# ME433_BB_SCHEM.net
KiCad netlist of a schematic drawn in EAGLE
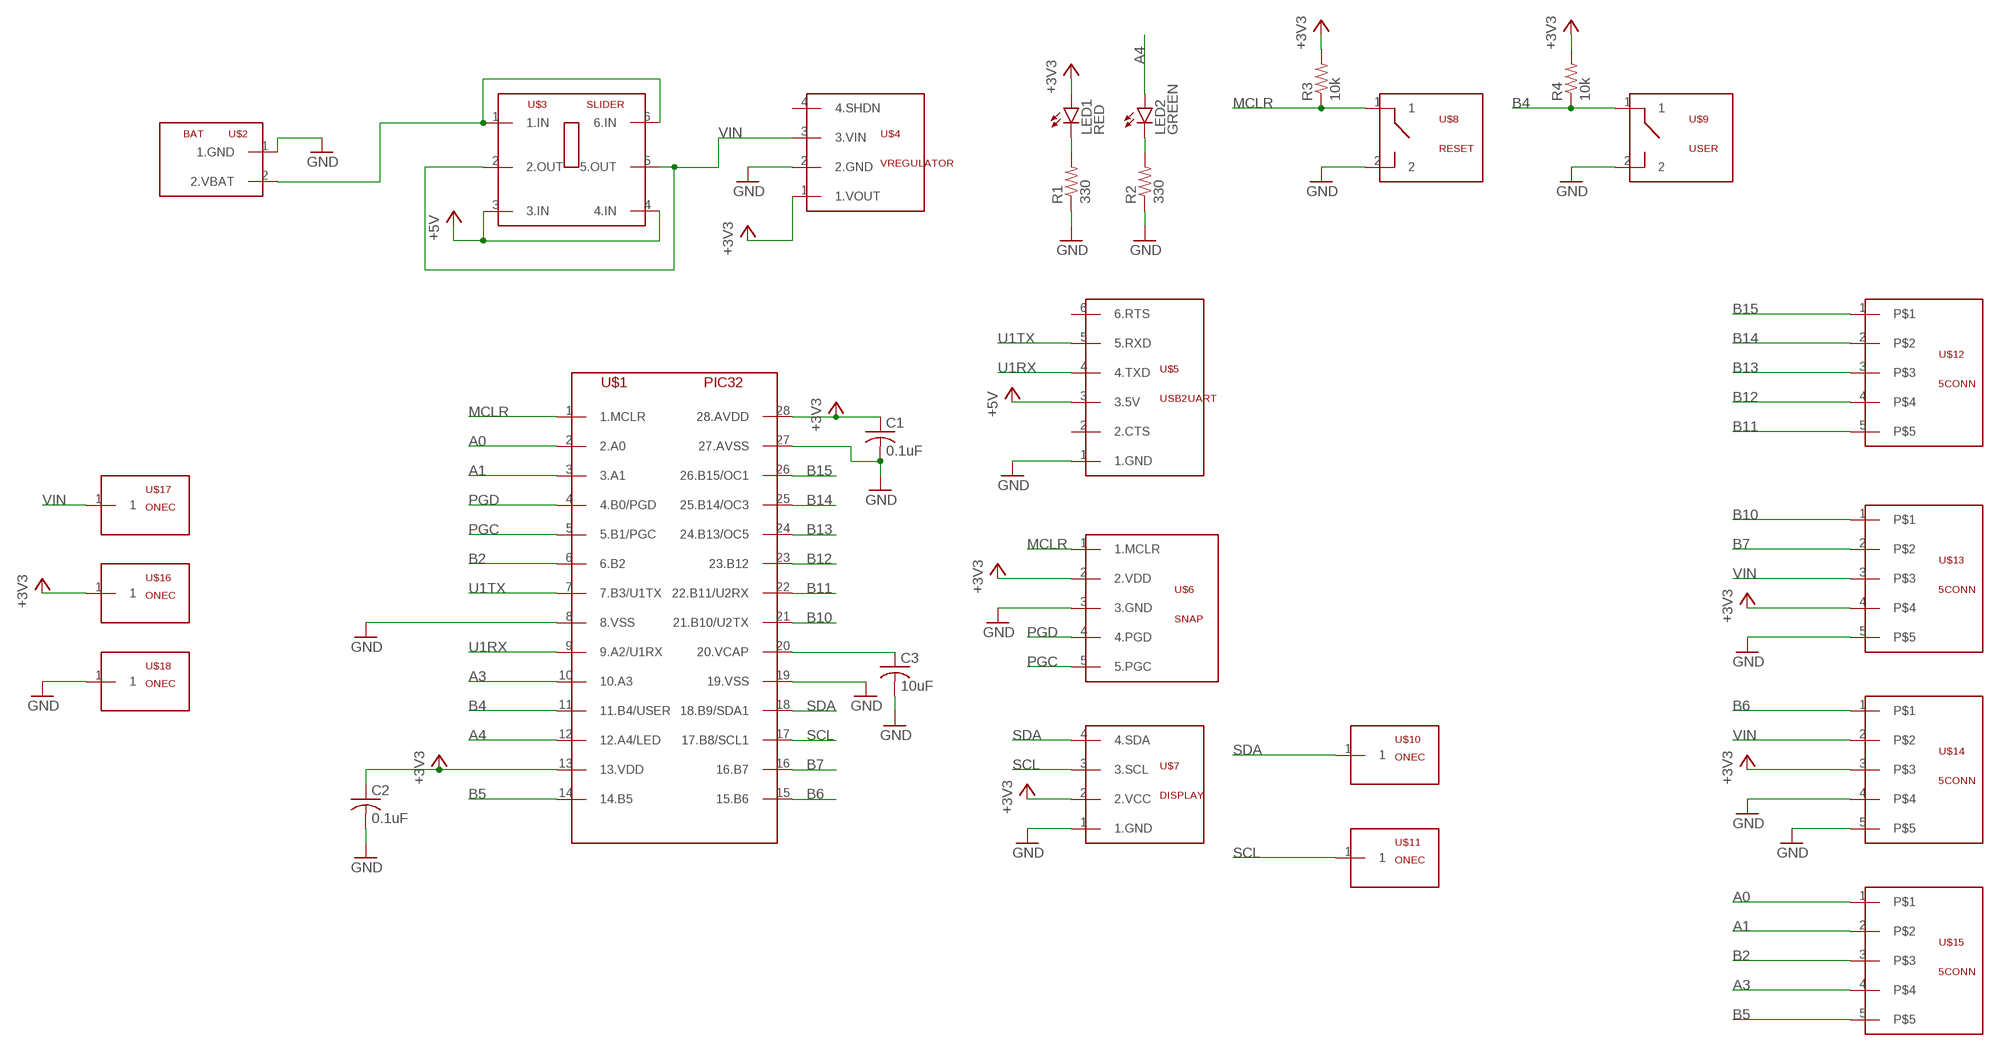
[diagram p0: schematic, sheet 1]

(export (version "E")
  (design (tool "Eeschema 10.0.6"))
  (components
    (comp (ref "C1")
      (value "0.1uF")
      (footprint "eagle-import:C025-024X044")
      (libsource (lib "eagle-import") (part "C-US025-024X044"))
    )
    (comp (ref "C2")
      (value "0.1uF")
      (footprint "eagle-import:C025-024X044")
      (libsource (lib "eagle-import") (part "C-US025-024X044"))
    )
    (comp (ref "C3")
      (value "10uF")
      (footprint "eagle-import:C025-024X044")
      (libsource (lib "eagle-import") (part "C-US025-024X044"))
    )
    (comp (ref "LED1")
      (value "RED")
      (footprint "eagle-import:LED3MM")
      (libsource (lib "eagle-import") (part "LED3MM"))
    )
    (comp (ref "LED2")
      (value "GREEN")
      (footprint "eagle-import:LED3MM")
      (libsource (lib "eagle-import") (part "LED3MM"))
    )
    (comp (ref "R1")
      (value "330")
      (footprint "eagle-import:0207_7")
      (libsource (lib "eagle-import") (part "R-US_0207/7"))
    )
    (comp (ref "R2")
      (value "330")
      (footprint "eagle-import:0207_7")
      (libsource (lib "eagle-import") (part "R-US_0207/7"))
    )
    (comp (ref "R3")
      (value "10k")
      (footprint "eagle-import:0207_7")
      (libsource (lib "eagle-import") (part "R-US_0207/7"))
    )
    (comp (ref "R4")
      (value "10k")
      (footprint "eagle-import:0207_7")
      (libsource (lib "eagle-import") (part "R-US_0207/7"))
    )
    (comp (ref "U$1")
      (value "PIC32")
      (footprint "eagle-import:DIL28-3")
      (libsource (lib "eagle-import") (part "PIC32"))
    )
    (comp (ref "U$2")
      (value "BAT")
      (footprint "eagle-import:BAT")
      (libsource (lib "eagle-import") (part "BAT"))
    )
    (comp (ref "U$3")
      (value "SLIDER")
      (footprint "eagle-import:SLIDER")
      (libsource (lib "eagle-import") (part "SLIDER"))
    )
    (comp (ref "U$4")
      (value "VREGULATOR")
      (footprint "eagle-import:VREGULATOR")
      (libsource (lib "eagle-import") (part "VREGULATOR"))
    )
    (comp (ref "U$5")
      (value "USB2UART")
      (footprint "eagle-import:USB2UART")
      (libsource (lib "eagle-import") (part "USB2UART"))
    )
    (comp (ref "U$6")
      (value "SNAP")
      (footprint "eagle-import:SNAP")
      (libsource (lib "eagle-import") (part "SNAP"))
    )
    (comp (ref "U$7")
      (value "DISPLAY")
      (footprint "eagle-import:DISPLAY")
      (libsource (lib "eagle-import") (part "DISPLAY"))
    )
    (comp (ref "U$8")
      (value "RESET")
      (footprint "eagle-import:BUTT")
      (libsource (lib "eagle-import") (part "BUTT"))
    )
    (comp (ref "U$9")
      (value "USER")
      (footprint "eagle-import:BUTT")
      (libsource (lib "eagle-import") (part "BUTT"))
    )
    (comp (ref "U$10")
      (value "ONEC")
      (footprint "eagle-import:ONEC")
      (libsource (lib "eagle-import") (part "ONEC"))
    )
    (comp (ref "U$11")
      (value "ONEC")
      (footprint "eagle-import:ONEC")
      (libsource (lib "eagle-import") (part "ONEC"))
    )
    (comp (ref "U$12")
      (value "5CONN")
      (footprint "eagle-import:5CONN")
      (libsource (lib "eagle-import") (part "5CONN"))
    )
    (comp (ref "U$13")
      (value "5CONN")
      (footprint "eagle-import:5CONN")
      (libsource (lib "eagle-import") (part "5CONN"))
    )
    (comp (ref "U$14")
      (value "5CONN")
      (footprint "eagle-import:5CONN")
      (libsource (lib "eagle-import") (part "5CONN"))
    )
    (comp (ref "U$15")
      (value "5CONN")
      (footprint "eagle-import:5CONN")
      (libsource (lib "eagle-import") (part "5CONN"))
    )
    (comp (ref "U$16")
      (value "ONEC")
      (footprint "eagle-import:ONEC")
      (libsource (lib "eagle-import") (part "ONEC"))
    )
    (comp (ref "U$17")
      (value "ONEC")
      (footprint "eagle-import:ONEC")
      (libsource (lib "eagle-import") (part "ONEC"))
    )
    (comp (ref "U$18")
      (value "ONEC")
      (footprint "eagle-import:ONEC")
      (libsource (lib "eagle-import") (part "ONEC"))
    )
  )
  (nets
    (net (code "1") (name "+3V3") (class "Default")
      (node (ref "C1") (pin "1") (pinfunction "1_1") (pintype "passive"))
      (node (ref "C2") (pin "1") (pinfunction "1_1") (pintype "passive"))
      (node (ref "LED1") (pin "A") (pinfunction "A_A") (pintype "passive"))
      (node (ref "R3") (pin "2") (pinfunction "2_2") (pintype "passive"))
      (node (ref "R4") (pin "2") (pinfunction "2_2") (pintype "passive"))
      (node (ref "U$1") (pin "13") (pinfunction "13.VDD_13") (pintype "bidirectional"))
      (node (ref "U$1") (pin "28") (pinfunction "28.AVDD_28") (pintype "bidirectional"))
      (node (ref "U$13") (pin "4") (pinfunction "P$4_4") (pintype "bidirectional"))
      (node (ref "U$14") (pin "3") (pinfunction "P$3_3") (pintype "bidirectional"))
      (node (ref "U$16") (pin "1") (pinfunction "1_1") (pintype "bidirectional"))
      (node (ref "U$4") (pin "1") (pinfunction "1.VOUT_1") (pintype "bidirectional"))
      (node (ref "U$6") (pin "2") (pinfunction "2.VDD_2") (pintype "bidirectional"))
      (node (ref "U$7") (pin "2") (pinfunction "2.VCC_2") (pintype "bidirectional"))
    )
    (net (code "2") (name "+5V") (class "Default")
      (node (ref "U$3") (pin "3") (pinfunction "3.IN_3") (pintype "bidirectional"))
      (node (ref "U$3") (pin "4") (pinfunction "4.IN_4") (pintype "bidirectional"))
      (node (ref "U$5") (pin "3") (pinfunction "3.5V_3") (pintype "bidirectional"))
    )
    (net (code "3") (name "/A0") (class "Default")
      (node (ref "U$1") (pin "2") (pinfunction "2.A0_2") (pintype "bidirectional"))
      (node (ref "U$15") (pin "1") (pinfunction "P$1_1") (pintype "bidirectional"))
    )
    (net (code "4") (name "/A1") (class "Default")
      (node (ref "U$1") (pin "3") (pinfunction "3.A1_3") (pintype "bidirectional"))
      (node (ref "U$15") (pin "2") (pinfunction "P$2_2") (pintype "bidirectional"))
    )
    (net (code "5") (name "/A3") (class "Default")
      (node (ref "U$1") (pin "10") (pinfunction "10.A3_10") (pintype "bidirectional"))
      (node (ref "U$15") (pin "4") (pinfunction "P$4_4") (pintype "bidirectional"))
    )
    (net (code "6") (name "/A4") (class "Default")
      (node (ref "LED2") (pin "A") (pinfunction "A_A") (pintype "passive"))
      (node (ref "U$1") (pin "12") (pinfunction "12.A4/LED_12") (pintype "bidirectional"))
    )
    (net (code "7") (name "/B2") (class "Default")
      (node (ref "U$1") (pin "6") (pinfunction "6.B2_6") (pintype "bidirectional"))
      (node (ref "U$15") (pin "3") (pinfunction "P$3_3") (pintype "bidirectional"))
    )
    (net (code "8") (name "/B4") (class "Default")
      (node (ref "R4") (pin "1") (pinfunction "1_1") (pintype "passive"))
      (node (ref "U$1") (pin "11") (pinfunction "11.B4/USER_11") (pintype "bidirectional"))
      (node (ref "U$9") (pin "1") (pinfunction "1_1") (pintype "bidirectional"))
    )
    (net (code "9") (name "/B5") (class "Default")
      (node (ref "U$1") (pin "14") (pinfunction "14.B5_14") (pintype "bidirectional"))
      (node (ref "U$15") (pin "5") (pinfunction "P$5_5") (pintype "bidirectional"))
    )
    (net (code "10") (name "/B6") (class "Default")
      (node (ref "U$1") (pin "15") (pinfunction "15.B6_15") (pintype "bidirectional"))
      (node (ref "U$14") (pin "1") (pinfunction "P$1_1") (pintype "bidirectional"))
    )
    (net (code "11") (name "/B7") (class "Default")
      (node (ref "U$1") (pin "16") (pinfunction "16.B7_16") (pintype "bidirectional"))
      (node (ref "U$13") (pin "2") (pinfunction "P$2_2") (pintype "bidirectional"))
    )
    (net (code "12") (name "/B10") (class "Default")
      (node (ref "U$1") (pin "21") (pinfunction "21.B10/U2TX_21") (pintype "bidirectional"))
      (node (ref "U$13") (pin "1") (pinfunction "P$1_1") (pintype "bidirectional"))
    )
    (net (code "13") (name "/B11") (class "Default")
      (node (ref "U$1") (pin "22") (pinfunction "22.B11/U2RX_22") (pintype "bidirectional"))
      (node (ref "U$12") (pin "5") (pinfunction "P$5_5") (pintype "bidirectional"))
    )
    (net (code "14") (name "/B12") (class "Default")
      (node (ref "U$1") (pin "23") (pinfunction "23.B12_23") (pintype "bidirectional"))
      (node (ref "U$12") (pin "4") (pinfunction "P$4_4") (pintype "bidirectional"))
    )
    (net (code "15") (name "/B13") (class "Default")
      (node (ref "U$1") (pin "24") (pinfunction "24.B13/OC5_24") (pintype "bidirectional"))
      (node (ref "U$12") (pin "3") (pinfunction "P$3_3") (pintype "bidirectional"))
    )
    (net (code "16") (name "/B14") (class "Default")
      (node (ref "U$1") (pin "25") (pinfunction "25.B14/OC3_25") (pintype "bidirectional"))
      (node (ref "U$12") (pin "2") (pinfunction "P$2_2") (pintype "bidirectional"))
    )
    (net (code "17") (name "/B15") (class "Default")
      (node (ref "U$1") (pin "26") (pinfunction "26.B15/OC1_26") (pintype "bidirectional"))
      (node (ref "U$12") (pin "1") (pinfunction "P$1_1") (pintype "bidirectional"))
    )
    (net (code "18") (name "/MCLR") (class "Default")
      (node (ref "R3") (pin "1") (pinfunction "1_1") (pintype "passive"))
      (node (ref "U$1") (pin "1") (pinfunction "1.MCLR_1") (pintype "bidirectional"))
      (node (ref "U$6") (pin "1") (pinfunction "1.MCLR_1") (pintype "bidirectional"))
      (node (ref "U$8") (pin "1") (pinfunction "1_1") (pintype "bidirectional"))
    )
    (net (code "19") (name "/PGC") (class "Default")
      (node (ref "U$1") (pin "5") (pinfunction "5.B1/PGC_5") (pintype "bidirectional"))
      (node (ref "U$6") (pin "5") (pinfunction "5.PGC_5") (pintype "bidirectional"))
    )
    (net (code "20") (name "/PGD") (class "Default")
      (node (ref "U$1") (pin "4") (pinfunction "4.B0/PGD_4") (pintype "bidirectional"))
      (node (ref "U$6") (pin "4") (pinfunction "4.PGD_4") (pintype "bidirectional"))
    )
    (net (code "21") (name "/SCL") (class "Default")
      (node (ref "U$1") (pin "17") (pinfunction "17.B8/SCL1_17") (pintype "bidirectional"))
      (node (ref "U$11") (pin "1") (pinfunction "1_1") (pintype "bidirectional"))
      (node (ref "U$7") (pin "3") (pinfunction "3.SCL_3") (pintype "bidirectional"))
    )
    (net (code "22") (name "/SDA") (class "Default")
      (node (ref "U$1") (pin "18") (pinfunction "18.B9/SDA1_18") (pintype "bidirectional"))
      (node (ref "U$10") (pin "1") (pinfunction "1_1") (pintype "bidirectional"))
      (node (ref "U$7") (pin "4") (pinfunction "4.SDA_4") (pintype "bidirectional"))
    )
    (net (code "23") (name "/U1RX") (class "Default")
      (node (ref "U$1") (pin "9") (pinfunction "9.A2/U1RX_9") (pintype "bidirectional"))
      (node (ref "U$5") (pin "4") (pinfunction "4.TXD_4") (pintype "bidirectional"))
    )
    (net (code "24") (name "/U1TX") (class "Default")
      (node (ref "U$1") (pin "7") (pinfunction "7.B3/U1TX_7") (pintype "bidirectional"))
      (node (ref "U$5") (pin "5") (pinfunction "5.RXD_5") (pintype "bidirectional"))
    )
    (net (code "25") (name "/VIN") (class "Default")
      (node (ref "U$13") (pin "3") (pinfunction "P$3_3") (pintype "bidirectional"))
      (node (ref "U$14") (pin "2") (pinfunction "P$2_2") (pintype "bidirectional"))
      (node (ref "U$17") (pin "1") (pinfunction "1_1") (pintype "bidirectional"))
      (node (ref "U$3") (pin "2") (pinfunction "2.OUT_2") (pintype "bidirectional"))
      (node (ref "U$3") (pin "5") (pinfunction "5.OUT_5") (pintype "bidirectional"))
      (node (ref "U$4") (pin "3") (pinfunction "3.VIN_3") (pintype "bidirectional"))
    )
    (net (code "26") (name "GND") (class "Default")
      (node (ref "C1") (pin "2") (pinfunction "2_2") (pintype "passive"))
      (node (ref "C2") (pin "2") (pinfunction "2_2") (pintype "passive"))
      (node (ref "C3") (pin "2") (pinfunction "2_2") (pintype "passive"))
      (node (ref "R1") (pin "1") (pinfunction "1_1") (pintype "passive"))
      (node (ref "R2") (pin "1") (pinfunction "1_1") (pintype "passive"))
      (node (ref "U$1") (pin "19") (pinfunction "19.VSS_19") (pintype "bidirectional"))
      (node (ref "U$1") (pin "27") (pinfunction "27.AVSS_27") (pintype "bidirectional"))
      (node (ref "U$1") (pin "8") (pinfunction "8.VSS_8") (pintype "bidirectional"))
      (node (ref "U$13") (pin "5") (pinfunction "P$5_5") (pintype "bidirectional"))
      (node (ref "U$14") (pin "4") (pinfunction "P$4_4") (pintype "bidirectional"))
      (node (ref "U$14") (pin "5") (pinfunction "P$5_5") (pintype "bidirectional"))
      (node (ref "U$18") (pin "1") (pinfunction "1_1") (pintype "bidirectional"))
      (node (ref "U$2") (pin "1") (pinfunction "1.GND_1") (pintype "bidirectional"))
      (node (ref "U$4") (pin "2") (pinfunction "2.GND_2") (pintype "bidirectional"))
      (node (ref "U$5") (pin "1") (pinfunction "1.GND_1") (pintype "bidirectional"))
      (node (ref "U$6") (pin "3") (pinfunction "3.GND_3") (pintype "bidirectional"))
      (node (ref "U$7") (pin "1") (pinfunction "1.GND_1") (pintype "bidirectional"))
      (node (ref "U$8") (pin "2") (pinfunction "2_2") (pintype "bidirectional"))
      (node (ref "U$9") (pin "2") (pinfunction "2_2") (pintype "bidirectional"))
    )
    (net (code "27") (name "Net-(LED1-C)") (class "Default")
      (node (ref "LED1") (pin "K") (pinfunction "C_K") (pintype "passive"))
      (node (ref "R1") (pin "2") (pinfunction "2_2") (pintype "passive"))
    )
    (net (code "28") (name "Net-(LED2-C)") (class "Default")
      (node (ref "LED2") (pin "K") (pinfunction "C_K") (pintype "passive"))
      (node (ref "R2") (pin "2") (pinfunction "2_2") (pintype "passive"))
    )
    (net (code "29") (name "Net-(U$1-20.VCAP)") (class "Default")
      (node (ref "C3") (pin "1") (pinfunction "1_1") (pintype "passive"))
      (node (ref "U$1") (pin "20") (pinfunction "20.VCAP_20") (pintype "bidirectional"))
    )
    (net (code "30") (name "Net-(U$2-2.VBAT)") (class "Default")
      (node (ref "U$2") (pin "2") (pinfunction "2.VBAT_2") (pintype "bidirectional"))
      (node (ref "U$3") (pin "1") (pinfunction "1.IN_1") (pintype "bidirectional"))
      (node (ref "U$3") (pin "6") (pinfunction "6.IN_6") (pintype "bidirectional"))
    )
    (net (code "31") (name "unconnected-(U$4-4.SHDN-Pad4)") (class "Default")
      (node (ref "U$4") (pin "4") (pinfunction "4.SHDN_4") (pintype "bidirectional"))
    )
    (net (code "32") (name "unconnected-(U$5-2.CTS-Pad2)") (class "Default")
      (node (ref "U$5") (pin "2") (pinfunction "2.CTS_2") (pintype "bidirectional"))
    )
    (net (code "33") (name "unconnected-(U$5-6.RTS-Pad6)") (class "Default")
      (node (ref "U$5") (pin "6") (pinfunction "6.RTS_6") (pintype "bidirectional"))
    )
  )
)
